# untitled.net
KiCad netlist of a schematic drawn in EAGLE
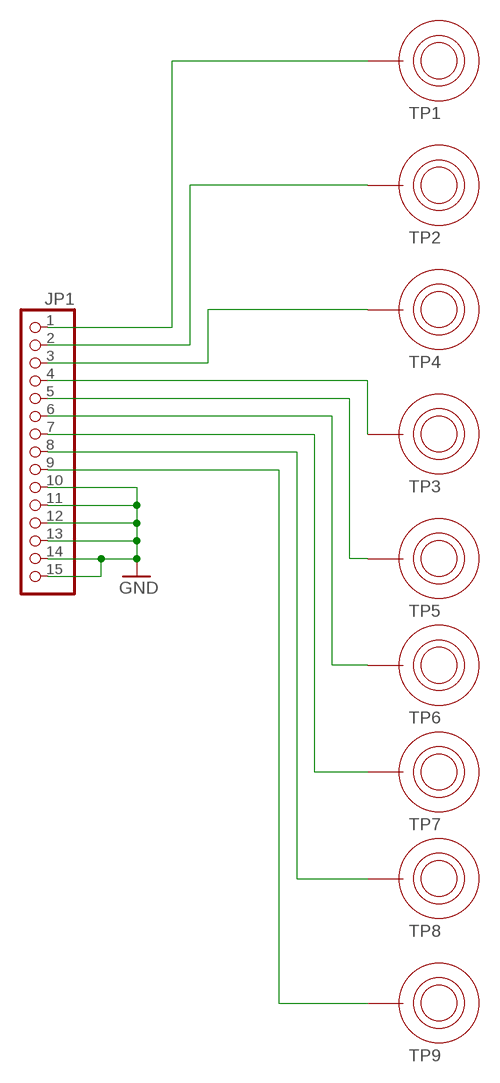
[diagram p0: schematic, sheet 1]

(export (version "E")
  (design (tool "Eeschema 10.0.6"))
  (components
    (comp (ref "JP1")
      (value "PINHD-1X15")
      (footprint "eagle-import:1X15")
      (libsource (lib "eagle-import") (part "PINHD-1X15"))
    )
    (comp (ref "TP1")
      (value "TOUCHPADROUND15MM")
      (footprint "eagle-import:TOUCHPAD_ROUND_15MM")
      (libsource (lib "eagle-import") (part "TOUCHPADROUND15MM"))
    )
    (comp (ref "TP2")
      (value "TOUCHPADROUND15MM")
      (footprint "eagle-import:TOUCHPAD_ROUND_15MM")
      (libsource (lib "eagle-import") (part "TOUCHPADROUND15MM"))
    )
    (comp (ref "TP3")
      (value "TOUCHPADROUND15MM")
      (footprint "eagle-import:TOUCHPAD_ROUND_15MM")
      (libsource (lib "eagle-import") (part "TOUCHPADROUND15MM"))
    )
    (comp (ref "TP4")
      (value "TOUCHPADROUND15MM")
      (footprint "eagle-import:TOUCHPAD_ROUND_15MM")
      (libsource (lib "eagle-import") (part "TOUCHPADROUND15MM"))
    )
    (comp (ref "TP5")
      (value "TOUCHPADROUND15MM")
      (footprint "eagle-import:TOUCHPAD_ROUND_15MM")
      (libsource (lib "eagle-import") (part "TOUCHPADROUND15MM"))
    )
    (comp (ref "TP6")
      (value "TOUCHPADROUND15MM")
      (footprint "eagle-import:TOUCHPAD_ROUND_15MM")
      (libsource (lib "eagle-import") (part "TOUCHPADROUND15MM"))
    )
    (comp (ref "TP7")
      (value "TOUCHPADROUND15MM")
      (footprint "eagle-import:TOUCHPAD_ROUND_15MM")
      (libsource (lib "eagle-import") (part "TOUCHPADROUND15MM"))
    )
    (comp (ref "TP8")
      (value "TOUCHPADROUND15MM")
      (footprint "eagle-import:TOUCHPAD_ROUND_15MM")
      (libsource (lib "eagle-import") (part "TOUCHPADROUND15MM"))
    )
    (comp (ref "TP9")
      (value "TOUCHPADROUND15MM")
      (footprint "eagle-import:TOUCHPAD_ROUND_15MM")
      (libsource (lib "eagle-import") (part "TOUCHPADROUND15MM"))
    )
  )
  (nets
    (net (code "1") (name "GND") (class "Default")
      (node (ref "JP1") (pin "10") (pinfunction "10_10") (pintype "passive"))
      (node (ref "JP1") (pin "11") (pinfunction "11_11") (pintype "passive"))
      (node (ref "JP1") (pin "12") (pinfunction "12_12") (pintype "passive"))
      (node (ref "JP1") (pin "13") (pinfunction "13_13") (pintype "passive"))
      (node (ref "JP1") (pin "14") (pinfunction "14_14") (pintype "passive"))
      (node (ref "JP1") (pin "15") (pinfunction "15_15") (pintype "passive"))
    )
    (net (code "2") (name "Net-(JP1-Pad1)") (class "Default")
      (node (ref "JP1") (pin "1") (pinfunction "1_1") (pintype "passive"))
      (node (ref "TP1") (pin "P$1") (pinfunction "P$1_P$1") (pintype "bidirectional"))
    )
    (net (code "3") (name "Net-(JP1-Pad2)") (class "Default")
      (node (ref "JP1") (pin "2") (pinfunction "2_2") (pintype "passive"))
      (node (ref "TP2") (pin "P$1") (pinfunction "P$1_P$1") (pintype "bidirectional"))
    )
    (net (code "4") (name "Net-(JP1-Pad3)") (class "Default")
      (node (ref "JP1") (pin "3") (pinfunction "3_3") (pintype "passive"))
      (node (ref "TP4") (pin "P$1") (pinfunction "P$1_P$1") (pintype "bidirectional"))
    )
    (net (code "5") (name "Net-(JP1-Pad4)") (class "Default")
      (node (ref "JP1") (pin "4") (pinfunction "4_4") (pintype "passive"))
      (node (ref "TP3") (pin "P$1") (pinfunction "P$1_P$1") (pintype "bidirectional"))
    )
    (net (code "6") (name "Net-(JP1-Pad5)") (class "Default")
      (node (ref "JP1") (pin "5") (pinfunction "5_5") (pintype "passive"))
      (node (ref "TP5") (pin "P$1") (pinfunction "P$1_P$1") (pintype "bidirectional"))
    )
    (net (code "7") (name "Net-(JP1-Pad6)") (class "Default")
      (node (ref "JP1") (pin "6") (pinfunction "6_6") (pintype "passive"))
      (node (ref "TP6") (pin "P$1") (pinfunction "P$1_P$1") (pintype "bidirectional"))
    )
    (net (code "8") (name "Net-(JP1-Pad7)") (class "Default")
      (node (ref "JP1") (pin "7") (pinfunction "7_7") (pintype "passive"))
      (node (ref "TP7") (pin "P$1") (pinfunction "P$1_P$1") (pintype "bidirectional"))
    )
    (net (code "9") (name "Net-(JP1-Pad8)") (class "Default")
      (node (ref "JP1") (pin "8") (pinfunction "8_8") (pintype "passive"))
      (node (ref "TP8") (pin "P$1") (pinfunction "P$1_P$1") (pintype "bidirectional"))
    )
    (net (code "10") (name "Net-(JP1-Pad9)") (class "Default")
      (node (ref "JP1") (pin "9") (pinfunction "9_9") (pintype "passive"))
      (node (ref "TP9") (pin "P$1") (pinfunction "P$1_P$1") (pintype "bidirectional"))
    )
  )
)
